# PowerRegulationSchematic.net
KiCad netlist of a schematic drawn in EAGLE
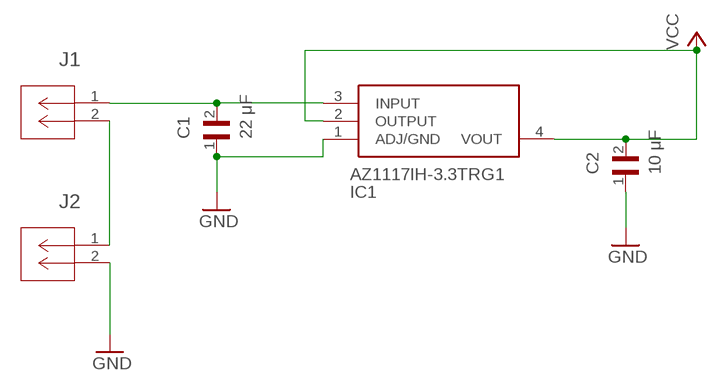
[diagram p0: schematic, sheet 1]

(export (version "E")
  (design (tool "Eeschema 10.0.6"))
  (components
    (comp (ref "C1")
      (value "22 μF")
      (footprint "eagle-import:CAPC2012X140N")
      (fields
        (field (name "DIGI-KEY_PART_NUMBER") "490-10511-1-ND")
        (field (name "MF") "Murata")
        (field (name "MP") "GRM21BR61A226ME51L")
      )
      (libsource (lib "eagle-import") (part "GRM21BR61A226ME51L"))
    )
    (comp (ref "C2")
      (value "10 μF")
      (footprint "eagle-import:CAPC2012X140N")
      (fields
        (field (name "DIGI-KEY_PART_NUMBER") "490-10516-1-ND")
        (field (name "MF") "Murata Electronics")
        (field (name "MP") "GRM21BR71A106KA73L")
      )
      (libsource (lib "eagle-import") (part "GRM21BR71A106KA73L"))
    )
    (comp (ref "IC1")
      (value "AZ1117IH-3.3TRG1")
      (footprint "eagle-import:SOT230P700X170-4N")
      (fields (field (name "MF") "Diodes Inc."))
      (libsource (lib "eagle-import") (part "AZ1117IH-3.3TRG1"))
    )
    (comp (ref "J1")
      (value "B2B-PH-K-S(LF)(SN)")
      (footprint "eagle-import:CONN_B2B-PH-K-S(LF)(SN)_JST")
      (fields (field (name "COPYRIGHT") "Copyright (C) 2018 Accelerated Designs. All rights reserved"))
      (libsource (lib "eagle-import") (part "B2B-PH-K-S(LF)(SN)"))
    )
    (comp (ref "J2")
      (value "B2B-PH-K-S(LF)(SN)")
      (footprint "eagle-import:CONN_B2B-PH-K-S(LF)(SN)_JST")
      (fields (field (name "COPYRIGHT") "Copyright (C) 2018 Accelerated Designs. All rights reserved"))
      (libsource (lib "eagle-import") (part "B2B-PH-K-S(LF)(SN)"))
    )
  )
  (nets
    (net (code "1") (name "GND") (class "Default")
      (node (ref "C1") (pin "1") (pinfunction "1_1") (pintype "passive"))
      (node (ref "C2") (pin "1") (pinfunction "1_1") (pintype "passive"))
      (node (ref "IC1") (pin "1") (pinfunction "ADJ/GND_1") (pintype "bidirectional"))
      (node (ref "J2") (pin "2") (pinfunction "2_2") (pintype "passive"))
    )
    (net (code "2") (name "Net-(IC1-INPUT)") (class "Default")
      (node (ref "C1") (pin "2") (pinfunction "2_2") (pintype "passive"))
      (node (ref "IC1") (pin "3") (pinfunction "INPUT_3") (pintype "bidirectional"))
      (node (ref "J1") (pin "1") (pinfunction "1_1") (pintype "passive"))
    )
    (net (code "3") (name "Net-(J1-Pad2)") (class "Default")
      (node (ref "J1") (pin "2") (pinfunction "2_2") (pintype "passive"))
      (node (ref "J2") (pin "1") (pinfunction "1_1") (pintype "passive"))
    )
    (net (code "4") (name "VCC") (class "Default")
      (node (ref "C2") (pin "2") (pinfunction "2_2") (pintype "passive"))
      (node (ref "IC1") (pin "2") (pinfunction "OUTPUT_2") (pintype "bidirectional"))
      (node (ref "IC1") (pin "4") (pinfunction "VOUT_4") (pintype "bidirectional"))
    )
  )
)
